# power.net
KiCad netlist of a schematic drawn in Altium Designer
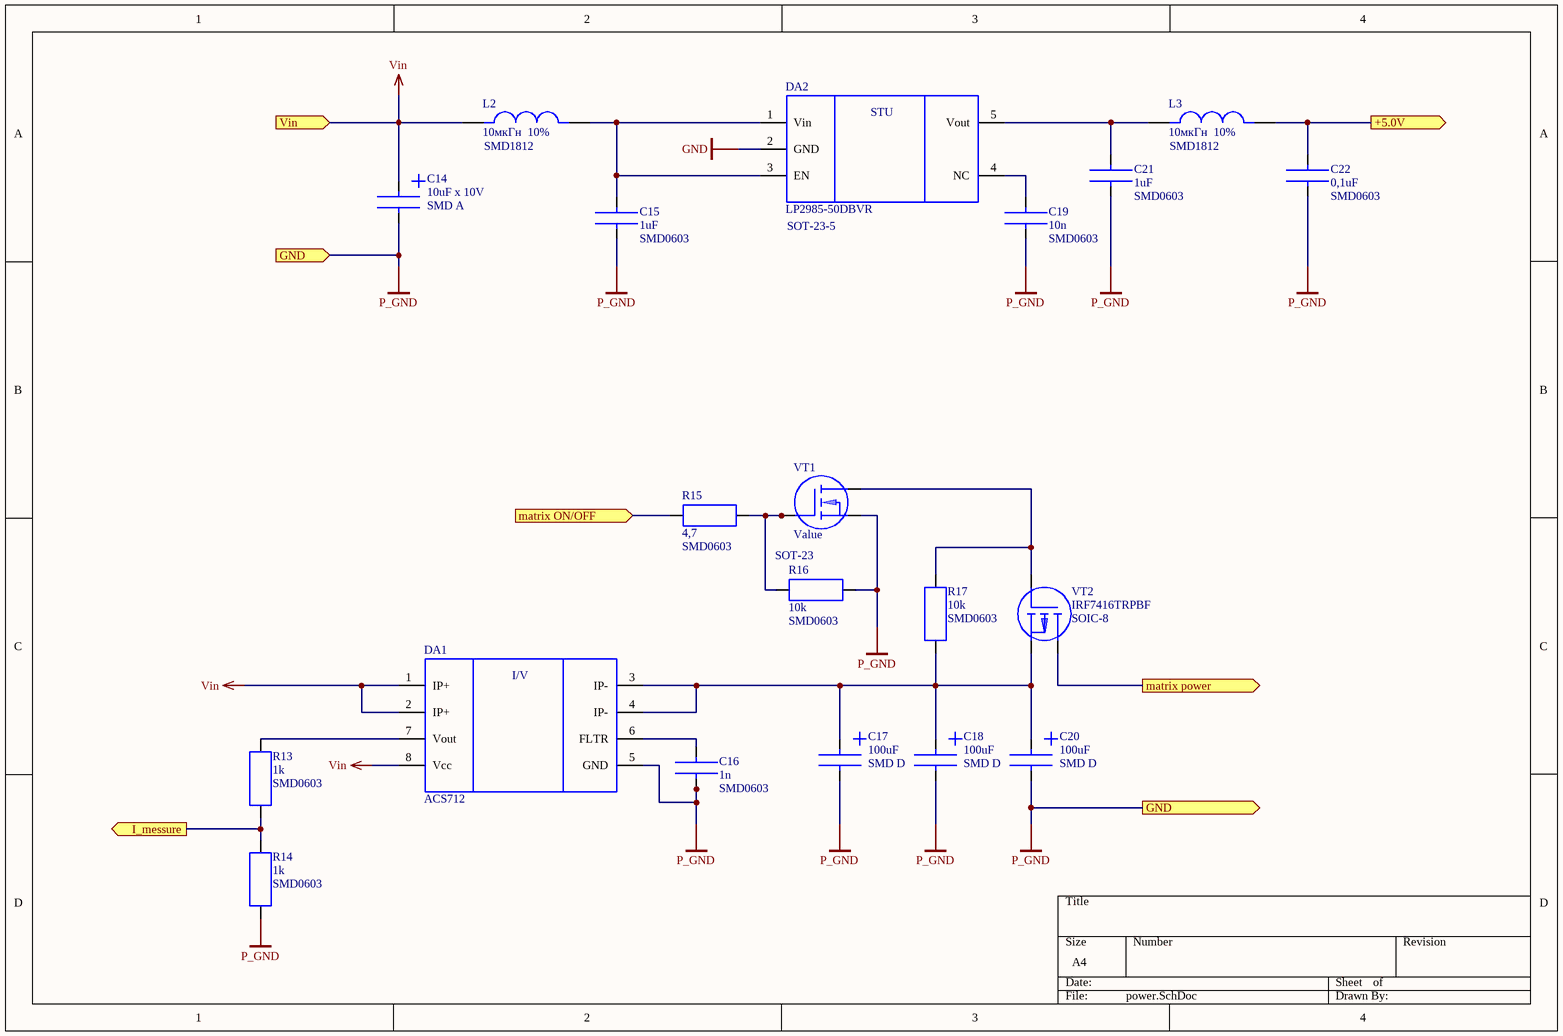
[diagram p0: power.SchDoc]

(export (version "E")
  (design (tool "Eeschema 10.0.6"))
  (components
    (comp (ref "C14")
      (value "10uF x 10V")
      (footprint "TANT_CAP_A(3216)")
      (fields (field (name "PACKAGE") "SMD A"))
      (libsource (lib "MechanikLibrary") (part "C_TANT_A"))
    )
    (comp (ref "C15")
      (value "1uF")
      (footprint "SMD0603(1005)")
      (fields (field (name "PACKAGE") "SMD0603"))
      (libsource (lib "MechanikLibrary") (part "CER_CUP_0603"))
    )
    (comp (ref "C16")
      (value "1n")
      (footprint "SMD0603(1005)")
      (fields (field (name "PACKAGE") "SMD0603"))
      (libsource (lib "MechanikLibrary") (part "CER_CUP_0603"))
    )
    (comp (ref "C17")
      (value "100uF")
      (footprint "TANT_CAP_D(7343)")
      (fields (field (name "PACKAGE") "SMD D"))
      (libsource (lib "MechanikLibrary") (part "C_TANT_D"))
    )
    (comp (ref "C18")
      (value "100uF")
      (footprint "TANT_CAP_D(7343)")
      (fields (field (name "PACKAGE") "SMD D"))
      (libsource (lib "MechanikLibrary") (part "C_TANT_D"))
    )
    (comp (ref "C19")
      (value "10n")
      (footprint "SMD0603(1005)")
      (fields (field (name "PACKAGE") "SMD0603"))
      (libsource (lib "MechanikLibrary") (part "CER_CUP_0603"))
    )
    (comp (ref "C20")
      (value "100uF")
      (footprint "TANT_CAP_D(7343)")
      (fields (field (name "PACKAGE") "SMD D"))
      (libsource (lib "MechanikLibrary") (part "C_TANT_D"))
    )
    (comp (ref "C21")
      (value "1uF")
      (footprint "SMD0603(1005)")
      (fields (field (name "PACKAGE") "SMD0603"))
      (libsource (lib "MechanikLibrary") (part "CER_CUP_0603"))
    )
    (comp (ref "C22")
      (value "0,1uF")
      (footprint "SMD0603(1005)")
      (fields (field (name "PACKAGE") "SMD0603"))
      (libsource (lib "MechanikLibrary") (part "CER_CUP_0603"))
    )
    (comp (ref "DA1")
      (value "ACS712")
      (footprint "SOIC8")
      (libsource (lib "MechanikLibrary") (part "Микросхема ACS712"))
    )
    (comp (ref "DA2")
      (value "LP2985-50DBVR")
      (footprint "SOT23-5")
      (fields (field (name "PACKAGE") "SOT-23-5"))
      (libsource (lib "MechanikLibrary") (part "LD3985M33R"))
    )
    (comp (ref "L2")
      (value "10мкГн  10%")
      (footprint "SMD2010(5025)")
      (fields (field (name "PACKAGE") "SMD1812"))
      (libsource (lib "MechanikLibrary") (part "L1"))
    )
    (comp (ref "L3")
      (value "10мкГн  10%")
      (footprint "SMD2010(5025)")
      (fields (field (name "PACKAGE") "SMD1812"))
      (libsource (lib "MechanikLibrary") (part "L1"))
    )
    (comp (ref "R13")
      (value "1k")
      (footprint "SMD0603(1005)")
      (fields (field (name "PACKAGE") "SMD0603"))
      (libsource (lib "MechanikLibrary") (part "R_0603"))
    )
    (comp (ref "R14")
      (value "1k")
      (footprint "SMD0603(1005)")
      (fields (field (name "PACKAGE") "SMD0603"))
      (libsource (lib "MechanikLibrary") (part "R_0603"))
    )
    (comp (ref "R15")
      (value "4,7")
      (footprint "SMD0603(1005)")
      (fields (field (name "PACKAGE") "SMD0603"))
      (libsource (lib "MechanikLibrary") (part "R_0603"))
    )
    (comp (ref "R16")
      (value "10k")
      (footprint "SMD0603(1005)")
      (fields (field (name "PACKAGE") "SMD0603"))
      (libsource (lib "MechanikLibrary") (part "R_0603"))
    )
    (comp (ref "R17")
      (value "10k")
      (footprint "SMD0603(1005)")
      (fields (field (name "PACKAGE") "SMD0603"))
      (libsource (lib "MechanikLibrary") (part "R_0603"))
    )
    (comp (ref "VT1")
      (value "Value")
      (footprint "SOT23-3")
      (fields (field (name "PACKAGE") "SOT-23"))
      (libsource (lib "MechanikLibrary") (part "VT_N_MOSFET_SOT23_3"))
    )
    (comp (ref "VT2")
      (value "IRF7416TRPBF")
      (footprint "VT_SOIC8")
      (fields (field (name "PACKAGE") "SOIC-8"))
      (libsource (lib "MechanikLibrary") (part "Транзистор IRF7416TRPBF"))
    )
  )
  (nets
    (net (code "1") (name "/+5.0V") (class "Default")
      (node (ref "C22") (pin "1") (pintype "passive"))
      (node (ref "L3") (pin "2") (pinfunction "IN1_2") (pintype "passive"))
    )
    (net (code "2") (name "/I_messure") (class "Default")
      (node (ref "R13") (pin "2") (pintype "passive"))
      (node (ref "R14") (pin "1") (pintype "passive"))
    )
    (net (code "3") (name "/matrix ON{slash}OFF") (class "Default")
      (node (ref "R15") (pin "1") (pintype "passive"))
    )
    (net (code "4") (name "/matrix power") (class "Default") (node (ref "VT2") (pin "3") (pintype "passive")))
    (net (code "5") (name "GND") (class "Default")
      (node (ref "C14") (pin "2") (pintype "passive"))
      (node (ref "C15") (pin "2") (pintype "passive"))
      (node (ref "C16") (pin "2") (pintype "passive"))
      (node (ref "C17") (pin "2") (pintype "passive"))
      (node (ref "C18") (pin "2") (pintype "passive"))
      (node (ref "C19") (pin "2") (pintype "passive"))
      (node (ref "C20") (pin "2") (pintype "passive"))
      (node (ref "C21") (pin "2") (pintype "passive"))
      (node (ref "C22") (pin "2") (pintype "passive"))
      (node (ref "DA1") (pin "5") (pinfunction "GND_5") (pintype "passive"))
      (node (ref "DA2") (pin "2") (pinfunction "GND_2") (pintype "passive"))
      (node (ref "R14") (pin "2") (pintype "passive"))
      (node (ref "R16") (pin "2") (pintype "passive"))
      (node (ref "VT1") (pin "2") (pintype "passive"))
    )
    (net (code "6") (name "Net-(C17-Pad1)") (class "Default")
      (node (ref "C17") (pin "1") (pintype "passive"))
      (node (ref "C18") (pin "1") (pintype "passive"))
      (node (ref "C20") (pin "1") (pintype "passive"))
      (node (ref "DA1") (pin "3") (pinfunction "IP-_3") (pintype "passive"))
      (node (ref "DA1") (pin "4") (pinfunction "IP-_4") (pintype "passive"))
      (node (ref "R17") (pin "2") (pintype "passive"))
      (node (ref "VT2") (pin "1") (pintype "passive"))
    )
    (net (code "7") (name "Net-(DA1-FLTR)") (class "Default")
      (node (ref "C16") (pin "1") (pintype "passive"))
      (node (ref "DA1") (pin "6") (pinfunction "FLTR_6") (pintype "passive"))
    )
    (net (code "8") (name "Net-(DA1-Vout)") (class "Default")
      (node (ref "DA1") (pin "7") (pinfunction "Vout_7") (pintype "passive"))
      (node (ref "R13") (pin "1") (pintype "passive"))
    )
    (net (code "9") (name "Net-(DA2-EN)") (class "Default")
      (node (ref "C15") (pin "1") (pintype "passive"))
      (node (ref "DA2") (pin "1") (pinfunction "Vin_1") (pintype "passive"))
      (node (ref "DA2") (pin "3") (pinfunction "EN_3") (pintype "passive"))
      (node (ref "L2") (pin "2") (pinfunction "IN1_2") (pintype "passive"))
    )
    (net (code "10") (name "Net-(DA2-NC)") (class "Default")
      (node (ref "C19") (pin "1") (pintype "passive"))
      (node (ref "DA2") (pin "4") (pinfunction "NC_4") (pintype "passive"))
    )
    (net (code "11") (name "Net-(DA2-Vout)") (class "Default")
      (node (ref "C21") (pin "1") (pintype "passive"))
      (node (ref "DA2") (pin "5") (pinfunction "Vout_5") (pintype "passive"))
      (node (ref "L3") (pin "1") (pinfunction "IN1_1") (pintype "passive"))
    )
    (net (code "12") (name "Net-(R15-Pad2)") (class "Default")
      (node (ref "R15") (pin "2") (pintype "passive"))
      (node (ref "R16") (pin "1") (pintype "passive"))
      (node (ref "VT1") (pin "1") (pintype "passive"))
    )
    (net (code "13") (name "Net-(R17-Pad1)") (class "Default")
      (node (ref "R17") (pin "1") (pintype "passive"))
      (node (ref "VT1") (pin "3") (pintype "passive"))
      (node (ref "VT2") (pin "2") (pintype "passive"))
    )
    (net (code "14") (name "Vin") (class "Default")
      (node (ref "C14") (pin "1") (pintype "passive"))
      (node (ref "DA1") (pin "1") (pinfunction "IP+_1") (pintype "passive"))
      (node (ref "DA1") (pin "2") (pinfunction "IP+_2") (pintype "passive"))
      (node (ref "DA1") (pin "8") (pinfunction "Vcc_8") (pintype "passive"))
      (node (ref "L2") (pin "1") (pinfunction "IN1_1") (pintype "passive"))
    )
  )
)
